# TA-1.net
KiCad netlist of a schematic drawn in EAGLE
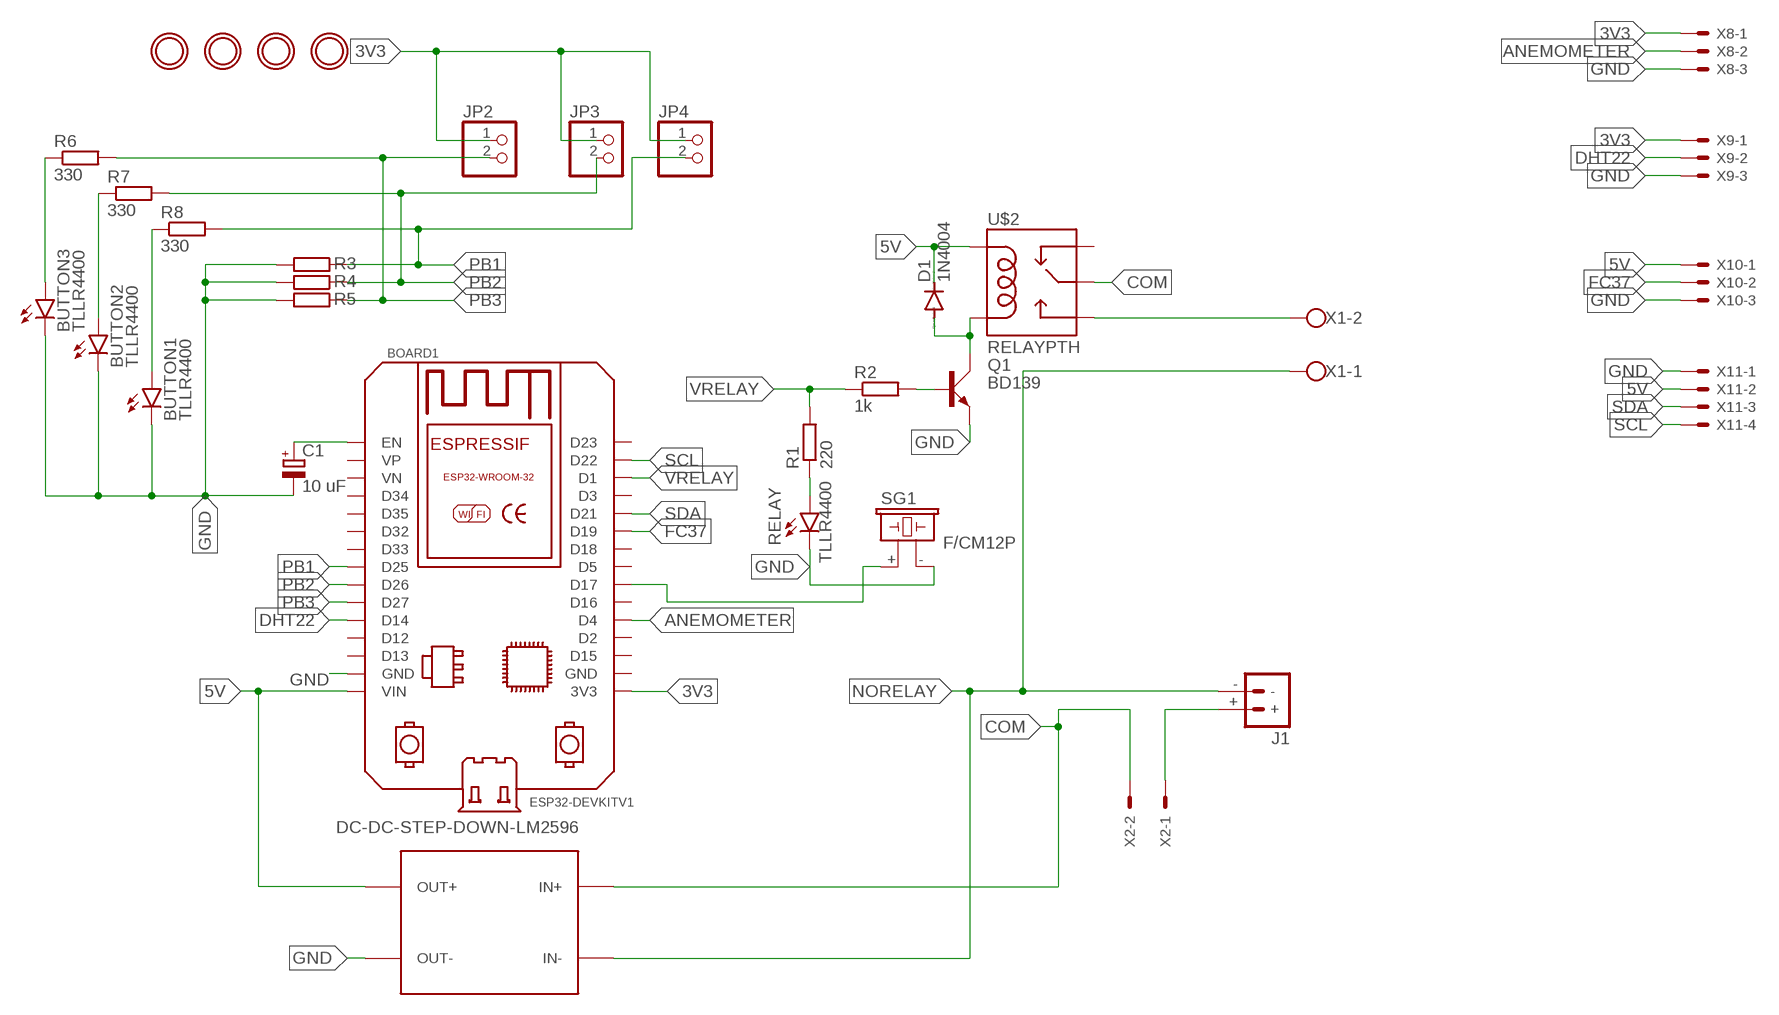
[diagram p0: schematic, sheet 1]

(export (version "E")
  (design (tool "Eeschema 10.0.6"))
  (components
    (comp (ref "BOARD1")
      (value "ESP32DEVKITV1")
      (footprint "eagle-import:ESP32-DEVKITV1")
      (libsource (lib "eagle-import") (part "ESP32DEVKITV1"))
    )
    (comp (ref "BUTTON1")
      (value "TLLR4400")
      (footprint "eagle-import:LED3MM")
      (fields (field (name "MF") "VISHAY SEMICONDUCTOR"))
      (libsource (lib "eagle-import") (part "TLLR4400"))
    )
    (comp (ref "BUTTON2")
      (value "TLLR4400")
      (footprint "eagle-import:LED3MM")
      (fields (field (name "MF") "VISHAY SEMICONDUCTOR"))
      (libsource (lib "eagle-import") (part "TLLR4400"))
    )
    (comp (ref "BUTTON3")
      (value "TLLR4400")
      (footprint "eagle-import:LED3MM")
      (fields (field (name "MF") "VISHAY SEMICONDUCTOR"))
      (libsource (lib "eagle-import") (part "TLLR4400"))
    )
    (comp (ref "C1")
      (value "10 uF")
      (footprint "eagle-import:E2,5-5")
      (libsource (lib "eagle-import") (part "CPOL-EUE2.5-5"))
    )
    (comp (ref "D1")
      (value "1N4004")
      (footprint "eagle-import:DO41-10")
      (libsource (lib "eagle-import") (part "1N4004"))
    )
    (comp (ref "J1")
      (value "BATTERY_CONN_DEANS")
      (footprint "eagle-import:DEANS")
      (libsource (lib "eagle-import") (part "BATTERY_CONN_DEANS"))
    )
    (comp (ref "JP2")
      (value "PINHD-1X2")
      (footprint "eagle-import:1X02")
      (libsource (lib "eagle-import") (part "PINHD-1X2"))
    )
    (comp (ref "JP3")
      (value "PINHD-1X2")
      (footprint "eagle-import:1X02")
      (libsource (lib "eagle-import") (part "PINHD-1X2"))
    )
    (comp (ref "JP4")
      (value "PINHD-1X2")
      (footprint "eagle-import:1X02")
      (libsource (lib "eagle-import") (part "PINHD-1X2"))
    )
    (comp (ref "Q1")
      (value "BD139")
      (footprint "eagle-import:TO126AV")
      (libsource (lib "eagle-import") (part "BD139"))
    )
    (comp (ref "R1")
      (value "220")
      (footprint "eagle-import:0207_10")
      (libsource (lib "eagle-import") (part "R-EU_0207/10"))
    )
    (comp (ref "R2")
      (value "1k")
      (footprint "eagle-import:0207_10")
      (libsource (lib "eagle-import") (part "R-EU_0207/10"))
    )
    (comp (ref "R3")
      (value "R-EU_0207/10")
      (footprint "eagle-import:0207_10")
      (libsource (lib "eagle-import") (part "R-EU_0207/10"))
    )
    (comp (ref "R4")
      (value "R-EU_0207/10")
      (footprint "eagle-import:0207_10")
      (libsource (lib "eagle-import") (part "R-EU_0207/10"))
    )
    (comp (ref "R5")
      (value "R-EU_0207/10")
      (footprint "eagle-import:0207_10")
      (libsource (lib "eagle-import") (part "R-EU_0207/10"))
    )
    (comp (ref "R6")
      (value "330")
      (footprint "eagle-import:0207_10")
      (libsource (lib "eagle-import") (part "R-EU_0207/10"))
    )
    (comp (ref "R7")
      (value "330")
      (footprint "eagle-import:0207_10")
      (libsource (lib "eagle-import") (part "R-EU_0207/10"))
    )
    (comp (ref "R8")
      (value "330")
      (footprint "eagle-import:0207_10")
      (libsource (lib "eagle-import") (part "R-EU_0207/10"))
    )
    (comp (ref "RELAY")
      (value "TLLR4400")
      (footprint "eagle-import:LED3MM")
      (fields (field (name "MF") "VISHAY SEMICONDUCTOR"))
      (libsource (lib "eagle-import") (part "TLLR4400"))
    )
    (comp (ref "SG1")
      (value "F/CM12P")
      (footprint "eagle-import:F_CM12P")
      (libsource (lib "eagle-import") (part "F/CM12P"))
    )
    (comp (ref "U$1")
      (value "MICROBUILDER_MOUNTINGHOLE3.0THIN")
      (footprint "eagle-import:MICROBUILDER_MOUNTINGHOLE_3.0_PLATEDTHIN")
      (libsource (lib "eagle-import") (part "MICROBUILDER_MOUNTINGHOLE3.0THIN"))
    )
    (comp (ref "U$2")
      (value "RELAYPTH")
      (footprint "eagle-import:SRD-05VDC-SL-C")
      (libsource (lib "eagle-import") (part "RELAYPTH"))
    )
    (comp (ref "U$3")
      (value "DC-DC-STEP-DOWN-LM2596")
      (footprint "eagle-import:DC-DC-STEP-DOWN-LM2596")
      (libsource (lib "eagle-import") (part "DC-DC-STEP-DOWN-LM2596"))
    )
    (comp (ref "U$4")
      (value "MICROBUILDER_MOUNTINGHOLE3.0THIN")
      (footprint "eagle-import:MICROBUILDER_MOUNTINGHOLE_3.0_PLATEDTHIN")
      (libsource (lib "eagle-import") (part "MICROBUILDER_MOUNTINGHOLE3.0THIN"))
    )
    (comp (ref "U$5")
      (value "MICROBUILDER_MOUNTINGHOLE3.0THIN")
      (footprint "eagle-import:MICROBUILDER_MOUNTINGHOLE_3.0_PLATEDTHIN")
      (libsource (lib "eagle-import") (part "MICROBUILDER_MOUNTINGHOLE3.0THIN"))
    )
    (comp (ref "U$6")
      (value "MICROBUILDER_MOUNTINGHOLE3.0THIN")
      (footprint "eagle-import:MICROBUILDER_MOUNTINGHOLE_3.0_PLATEDTHIN")
      (libsource (lib "eagle-import") (part "MICROBUILDER_MOUNTINGHOLE3.0THIN"))
    )
    (comp (ref "X1")
      (value "W237-102")
      (footprint "eagle-import:W237-102")
      (fields (field (name "MPN") "237-102"))
      (libsource (lib "eagle-import") (part "W237-102"))
    )
    (comp (ref "X2")
      (value "KK-156-2")
      (footprint "eagle-import:KK-156-2")
      (libsource (lib "eagle-import") (part "KK-156-2"))
    )
    (comp (ref "X8")
      (value "KK-156-3")
      (footprint "eagle-import:KK-156-3")
      (fields (field (name "MF") "MOLEX"))
      (libsource (lib "eagle-import") (part "KK-156-3"))
    )
    (comp (ref "X9")
      (value "KK-156-3")
      (footprint "eagle-import:KK-156-3")
      (fields (field (name "MF") "MOLEX"))
      (libsource (lib "eagle-import") (part "KK-156-3"))
    )
    (comp (ref "X10")
      (value "KK-156-3")
      (footprint "eagle-import:KK-156-3")
      (fields (field (name "MF") "MOLEX"))
      (libsource (lib "eagle-import") (part "KK-156-3"))
    )
    (comp (ref "X11")
      (value "KK-156-4")
      (footprint "eagle-import:KK-156-4")
      (fields (field (name "MF") "MOLEX"))
      (libsource (lib "eagle-import") (part "KK-156-4"))
    )
  )
  (nets
    (net (code "1") (name "3V3") (class "Default")
      (node (ref "BOARD1") (pin "3V3") (pinfunction "3V3_3V3") (pintype "bidirectional"))
      (node (ref "JP2") (pin "1") (pinfunction "1_1") (pintype "passive"))
      (node (ref "JP3") (pin "1") (pinfunction "1_1") (pintype "passive"))
      (node (ref "JP4") (pin "1") (pinfunction "1_1") (pintype "passive"))
      (node (ref "X8") (pin "1") (pinfunction "S_1") (pintype "passive"))
      (node (ref "X9") (pin "1") (pinfunction "S_1") (pintype "passive"))
    )
    (net (code "2") (name "5V") (class "Default")
      (node (ref "BOARD1") (pin "VIN") (pinfunction "VIN_VIN") (pintype "bidirectional"))
      (node (ref "D1") (pin "C") (pinfunction "C_C") (pintype "passive"))
      (node (ref "U$2") (pin "COIL1") (pinfunction "COIL1_COIL1") (pintype "bidirectional"))
      (node (ref "U$3") (pin "OUT+") (pinfunction "OUT+_OUT+") (pintype "bidirectional"))
      (node (ref "X10") (pin "1") (pinfunction "S_1") (pintype "passive"))
      (node (ref "X11") (pin "2") (pinfunction "S_2") (pintype "passive"))
    )
    (net (code "3") (name "ANEMOMETER") (class "Default")
      (node (ref "BOARD1") (pin "D4") (pinfunction "D4_D4") (pintype "bidirectional"))
      (node (ref "X8") (pin "2") (pinfunction "S_2") (pintype "passive"))
    )
    (net (code "4") (name "COM") (class "Default")
      (node (ref "U$2") (pin "SWCOMMON") (pinfunction "SWCOMMON_SWCOMMON") (pintype "bidirectional"))
      (node (ref "U$3") (pin "IN+") (pinfunction "IN+_IN+") (pintype "bidirectional"))
      (node (ref "X2") (pin "2") (pinfunction "S_2") (pintype "passive"))
    )
    (net (code "5") (name "DHT22") (class "Default")
      (node (ref "BOARD1") (pin "D14") (pinfunction "D14_D14") (pintype "bidirectional"))
      (node (ref "X9") (pin "2") (pinfunction "S_2") (pintype "passive"))
    )
    (net (code "6") (name "FC37") (class "Default")
      (node (ref "BOARD1") (pin "D19") (pinfunction "D19_D19") (pintype "bidirectional"))
      (node (ref "X10") (pin "2") (pinfunction "S_2") (pintype "passive"))
    )
    (net (code "7") (name "GND") (class "Default")
      (node (ref "BOARD1") (pin "GND") (pinfunction "GND_GND") (pintype "bidirectional"))
      (node (ref "BUTTON1") (pin "K") (pinfunction "C_K") (pintype "passive"))
      (node (ref "BUTTON2") (pin "K") (pinfunction "C_K") (pintype "passive"))
      (node (ref "BUTTON3") (pin "K") (pinfunction "C_K") (pintype "passive"))
      (node (ref "C1") (pin "-") (pinfunction "-_-") (pintype "passive"))
      (node (ref "Q1") (pin "E") (pinfunction "E_E") (pintype "passive"))
      (node (ref "R3") (pin "2") (pinfunction "2_2") (pintype "passive"))
      (node (ref "R4") (pin "2") (pinfunction "2_2") (pintype "passive"))
      (node (ref "R5") (pin "2") (pinfunction "2_2") (pintype "passive"))
      (node (ref "RELAY") (pin "K") (pinfunction "C_K") (pintype "passive"))
      (node (ref "SG1") (pin "-") (pinfunction "2_-") (pintype "passive"))
      (node (ref "U$3") (pin "OUT-") (pinfunction "OUT-_OUT-") (pintype "bidirectional"))
      (node (ref "X10") (pin "3") (pinfunction "S_3") (pintype "passive"))
      (node (ref "X11") (pin "1") (pinfunction "S_1") (pintype "passive"))
      (node (ref "X8") (pin "3") (pinfunction "S_3") (pintype "passive"))
      (node (ref "X9") (pin "3") (pinfunction "S_3") (pintype "passive"))
    )
    (net (code "8") (name "NORELAY") (class "Default")
      (node (ref "J1") (pin "-") (pinfunction "-_-") (pintype "passive"))
      (node (ref "U$3") (pin "IN-") (pinfunction "IN-_IN-") (pintype "bidirectional"))
      (node (ref "X1") (pin "1") (pinfunction "KL_1") (pintype "passive"))
    )
    (net (code "9") (name "Net-(BOARD1-PadEN)") (class "Default")
      (node (ref "BOARD1") (pin "EN") (pinfunction "EN_EN") (pintype "bidirectional"))
      (node (ref "C1") (pin "+") (pinfunction "+_+") (pintype "passive"))
    )
    (net (code "10") (name "Net-(BUTTON1-PadA)") (class "Default")
      (node (ref "BUTTON1") (pin "A") (pinfunction "A_A") (pintype "passive"))
      (node (ref "R8") (pin "1") (pinfunction "1_1") (pintype "passive"))
    )
    (net (code "11") (name "Net-(BUTTON2-PadA)") (class "Default")
      (node (ref "BUTTON2") (pin "A") (pinfunction "A_A") (pintype "passive"))
      (node (ref "R7") (pin "1") (pinfunction "1_1") (pintype "passive"))
    )
    (net (code "12") (name "Net-(BUTTON3-PadA)") (class "Default")
      (node (ref "BUTTON3") (pin "A") (pinfunction "A_A") (pintype "passive"))
      (node (ref "R6") (pin "1") (pinfunction "1_1") (pintype "passive"))
    )
    (net (code "13") (name "Net-(D1-PadA)") (class "Default")
      (node (ref "D1") (pin "A") (pinfunction "A_A") (pintype "passive"))
      (node (ref "Q1") (pin "C") (pinfunction "C_C") (pintype "passive"))
      (node (ref "U$2") (pin "COIL0") (pinfunction "COIL0_COIL0") (pintype "bidirectional"))
    )
    (net (code "14") (name "Net-(Q1-PadB)") (class "Default")
      (node (ref "Q1") (pin "B") (pinfunction "B_B") (pintype "passive"))
      (node (ref "R2") (pin "2") (pinfunction "2_2") (pintype "passive"))
    )
    (net (code "15") (name "Net-(R1-Pad1)") (class "Default")
      (node (ref "R1") (pin "1") (pinfunction "1_1") (pintype "passive"))
      (node (ref "RELAY") (pin "A") (pinfunction "A_A") (pintype "passive"))
    )
    (net (code "16") (name "Net-(SG1-1)") (class "Default")
      (node (ref "BOARD1") (pin "D17") (pinfunction "D17_D17") (pintype "bidirectional"))
      (node (ref "SG1") (pin "+") (pinfunction "1_+") (pintype "passive"))
    )
    (net (code "17") (name "Net-(X1B-KL)") (class "Default")
      (node (ref "U$2") (pin "SWOPEN") (pinfunction "SWOPEN_SWOPEN") (pintype "bidirectional"))
      (node (ref "X1") (pin "2") (pinfunction "KL_2") (pintype "passive"))
    )
    (net (code "18") (name "Net-(X2A-S)") (class "Default")
      (node (ref "J1") (pin "+") (pinfunction "+_+") (pintype "passive"))
      (node (ref "X2") (pin "1") (pinfunction "S_1") (pintype "passive"))
    )
    (net (code "19") (name "PB1") (class "Default")
      (node (ref "BOARD1") (pin "D25") (pinfunction "D25_D25") (pintype "bidirectional"))
      (node (ref "JP4") (pin "2") (pinfunction "2_2") (pintype "passive"))
      (node (ref "R3") (pin "1") (pinfunction "1_1") (pintype "passive"))
      (node (ref "R8") (pin "2") (pinfunction "2_2") (pintype "passive"))
    )
    (net (code "20") (name "PB2") (class "Default")
      (node (ref "BOARD1") (pin "D26") (pinfunction "D26_D26") (pintype "bidirectional"))
      (node (ref "JP3") (pin "2") (pinfunction "2_2") (pintype "passive"))
      (node (ref "R4") (pin "1") (pinfunction "1_1") (pintype "passive"))
      (node (ref "R7") (pin "2") (pinfunction "2_2") (pintype "passive"))
    )
    (net (code "21") (name "PB3") (class "Default")
      (node (ref "BOARD1") (pin "D27") (pinfunction "D27_D27") (pintype "bidirectional"))
      (node (ref "JP2") (pin "2") (pinfunction "2_2") (pintype "passive"))
      (node (ref "R5") (pin "1") (pinfunction "1_1") (pintype "passive"))
      (node (ref "R6") (pin "2") (pinfunction "2_2") (pintype "passive"))
    )
    (net (code "22") (name "SCL") (class "Default")
      (node (ref "BOARD1") (pin "D22") (pinfunction "D22_D22") (pintype "bidirectional"))
      (node (ref "X11") (pin "4") (pinfunction "S_4") (pintype "passive"))
    )
    (net (code "23") (name "SDA") (class "Default")
      (node (ref "BOARD1") (pin "D21") (pinfunction "D21_D21") (pintype "bidirectional"))
      (node (ref "X11") (pin "3") (pinfunction "S_3") (pintype "passive"))
    )
    (net (code "24") (name "VRELAY") (class "Default")
      (node (ref "BOARD1") (pin "D1") (pinfunction "D1_D1") (pintype "bidirectional"))
      (node (ref "R1") (pin "2") (pinfunction "2_2") (pintype "passive"))
      (node (ref "R2") (pin "1") (pinfunction "1_1") (pintype "passive"))
    )
    (net (code "25") (name "unconnected-(BOARD1-GND-PadGND@1)") (class "Default")
      (node (ref "BOARD1") (pin "GND@1") (pinfunction "GND_GND@1") (pintype "bidirectional"))
    )
    (net (code "26") (name "unconnected-(BOARD1-PadD2)") (class "Default")
      (node (ref "BOARD1") (pin "D2") (pinfunction "D2_D2") (pintype "bidirectional"))
    )
    (net (code "27") (name "unconnected-(BOARD1-PadD3)") (class "Default")
      (node (ref "BOARD1") (pin "D3") (pinfunction "D3_D3") (pintype "bidirectional"))
    )
    (net (code "28") (name "unconnected-(BOARD1-PadD5)") (class "Default")
      (node (ref "BOARD1") (pin "D5") (pinfunction "D5_D5") (pintype "bidirectional"))
    )
    (net (code "29") (name "unconnected-(BOARD1-PadD12)") (class "Default")
      (node (ref "BOARD1") (pin "D12") (pinfunction "D12_D12") (pintype "bidirectional"))
    )
    (net (code "30") (name "unconnected-(BOARD1-PadD13)") (class "Default")
      (node (ref "BOARD1") (pin "D13") (pinfunction "D13_D13") (pintype "bidirectional"))
    )
    (net (code "31") (name "unconnected-(BOARD1-PadD15)") (class "Default")
      (node (ref "BOARD1") (pin "D15") (pinfunction "D15_D15") (pintype "bidirectional"))
    )
    (net (code "32") (name "unconnected-(BOARD1-PadD16)") (class "Default")
      (node (ref "BOARD1") (pin "D16") (pinfunction "D16_D16") (pintype "bidirectional"))
    )
    (net (code "33") (name "unconnected-(BOARD1-PadD18)") (class "Default")
      (node (ref "BOARD1") (pin "D18") (pinfunction "D18_D18") (pintype "bidirectional"))
    )
    (net (code "34") (name "unconnected-(BOARD1-PadD23)") (class "Default")
      (node (ref "BOARD1") (pin "D23") (pinfunction "D23_D23") (pintype "bidirectional"))
    )
    (net (code "35") (name "unconnected-(BOARD1-PadD32)") (class "Default")
      (node (ref "BOARD1") (pin "D32") (pinfunction "D32_D32") (pintype "bidirectional"))
    )
    (net (code "36") (name "unconnected-(BOARD1-PadD33)") (class "Default")
      (node (ref "BOARD1") (pin "D33") (pinfunction "D33_D33") (pintype "bidirectional"))
    )
    (net (code "37") (name "unconnected-(BOARD1-PadD34)") (class "Default")
      (node (ref "BOARD1") (pin "D34") (pinfunction "D34_D34") (pintype "bidirectional"))
    )
    (net (code "38") (name "unconnected-(BOARD1-PadD35)") (class "Default")
      (node (ref "BOARD1") (pin "D35") (pinfunction "D35_D35") (pintype "bidirectional"))
    )
    (net (code "39") (name "unconnected-(BOARD1-PadVN)") (class "Default")
      (node (ref "BOARD1") (pin "VN") (pinfunction "VN_VN") (pintype "bidirectional"))
    )
    (net (code "40") (name "unconnected-(BOARD1-PadVP)") (class "Default")
      (node (ref "BOARD1") (pin "VP") (pinfunction "VP_VP") (pintype "bidirectional"))
    )
    (net (code "41") (name "unconnected-(U$2-SWCLOSE-PadSWCLOSED)") (class "Default")
      (node (ref "U$2") (pin "SWCLOSED") (pinfunction "SWCLOSE_SWCLOSED") (pintype "bidirectional"))
    )
  )
)
